# Flash-Memory.net
KiCad netlist of a schematic drawn in Altium Designer
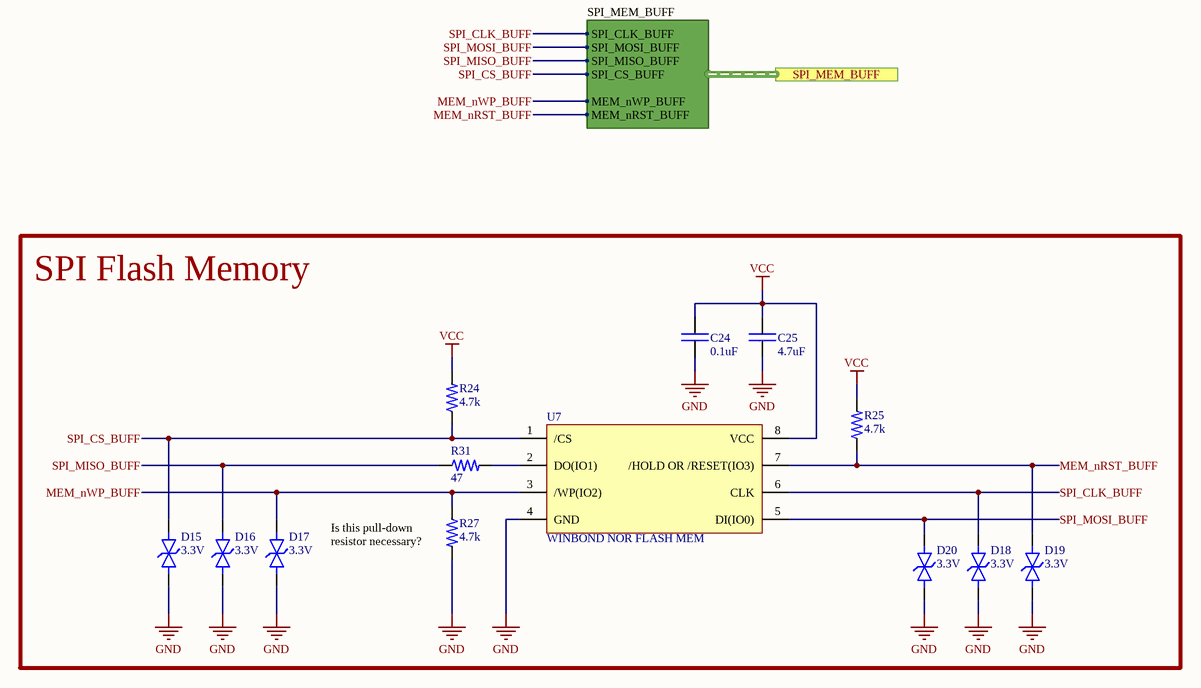
[diagram p0: Flash-Memory.SchDoc]

(export (version "E")
  (design (tool "Eeschema 10.0.6"))
  (components
    (comp (ref "C24")
      (value "0.1uF")
      (footprint "Beethoven-clock:0402C")
      (description "Capacitor")
      (fields (field (name "MFR") "Murata Electronics") (field (name "Comment") "CAP"))
      (libsource (lib "Beethoven-clock") (part "CAP"))
    )
    (comp (ref "C25")
      (value "4.7uF")
      (footprint "Beethoven-clock:0402C")
      (description "Capacitor")
      (fields (field (name "MFR") "Murata Electronics") (field (name "Comment") "CAP"))
      (libsource (lib "Beethoven-clock") (part "CAP"))
    )
    (comp (ref "D15")
      (value "DESD3V3E1BL-7B")
      (footprint "Beethoven-clock:0402-TVS")
      (description "TVS DIODE 3.3VWM 7VC DFN1006-2")
      (fields (field (name "MFR") "Diodes Incorporated") (field (name "VRS") "3.3V"))
      (libsource (lib "Beethoven-clock") (part "TVS Diode 3.3V Bi"))
    )
    (comp (ref "D16")
      (value "DESD3V3E1BL-7B")
      (footprint "Beethoven-clock:0402-TVS")
      (description "TVS DIODE 3.3VWM 7VC DFN1006-2")
      (fields (field (name "MFR") "Diodes Incorporated") (field (name "VRS") "3.3V"))
      (libsource (lib "Beethoven-clock") (part "TVS Diode 3.3V Bi"))
    )
    (comp (ref "D17")
      (value "DESD3V3E1BL-7B")
      (footprint "Beethoven-clock:0402-TVS")
      (description "TVS DIODE 3.3VWM 7VC DFN1006-2")
      (fields (field (name "MFR") "Diodes Incorporated") (field (name "VRS") "3.3V"))
      (libsource (lib "Beethoven-clock") (part "TVS Diode 3.3V Bi"))
    )
    (comp (ref "D18")
      (value "DESD3V3E1BL-7B")
      (footprint "Beethoven-clock:0402-TVS")
      (description "TVS DIODE 3.3VWM 7VC DFN1006-2")
      (fields (field (name "MFR") "Diodes Incorporated") (field (name "VRS") "3.3V"))
      (libsource (lib "Beethoven-clock") (part "TVS Diode 3.3V Bi"))
    )
    (comp (ref "D19")
      (value "DESD3V3E1BL-7B")
      (footprint "Beethoven-clock:0402-TVS")
      (description "TVS DIODE 3.3VWM 7VC DFN1006-2")
      (fields (field (name "MFR") "Diodes Incorporated") (field (name "VRS") "3.3V"))
      (libsource (lib "Beethoven-clock") (part "TVS Diode 3.3V Bi"))
    )
    (comp (ref "D20")
      (value "DESD3V3E1BL-7B")
      (footprint "Beethoven-clock:0402-TVS")
      (description "TVS DIODE 3.3VWM 7VC DFN1006-2")
      (fields (field (name "MFR") "Diodes Incorporated") (field (name "VRS") "3.3V"))
      (libsource (lib "Beethoven-clock") (part "TVS Diode 3.3V Bi"))
    )
    (comp (ref "R24")
      (value "4.7k")
      (footprint "Beethoven-clock:0402R")
      (description "Resistor")
      (fields (field (name "MFR") "YAGEO") (field (name "Comment") "RES"))
      (libsource (lib "Beethoven-clock") (part "RES"))
    )
    (comp (ref "R25")
      (value "4.7k")
      (footprint "Beethoven-clock:0402R")
      (description "Resistor")
      (fields (field (name "MFR") "YAGEO") (field (name "Comment") "RES"))
      (libsource (lib "Beethoven-clock") (part "RES"))
    )
    (comp (ref "R27")
      (value "4.7k")
      (footprint "Beethoven-clock:0402R")
      (description "Resistor")
      (fields (field (name "MFR") "YAGEO") (field (name "Comment") "RES"))
      (libsource (lib "Beethoven-clock") (part "RES"))
    )
    (comp (ref "R31")
      (value "47")
      (footprint "Beethoven-clock:0402R")
      (description "Resistor")
      (fields (field (name "MFR") "YAGEO") (field (name "Comment") "RES"))
      (libsource (lib "Beethoven-clock") (part "RES"))
    )
    (comp (ref "U7")
      (value "WINBOND NOR FLASH MEM")
      (footprint "Beethoven-clock:8-SOIC")
      (description "FLASH - NOR Memory IC SPI")
      (fields (field (name "MFR") "Winbond"))
      (libsource (lib "Beethoven-clock") (part "WINBOND NOR FLASH MEM"))
    )
  )
  (nets
    (net (code "2") (name "/MEM_nRST_BUFF") (class "Default")
      (node (ref "D19") (pin "1") (pinfunction "1_1") (pintype "passive"))
      (node (ref "R25") (pin "1") (pinfunction "1_1") (pintype "passive"))
      (node (ref "U7") (pin "7") (pinfunction "/HOLD_OR_/RESET(IO3)_7") (pintype "passive"))
    )
    (net (code "3") (name "/MEM_nWP_BUFF") (class "Default")
      (node (ref "D17") (pin "1") (pinfunction "1_1") (pintype "passive"))
      (node (ref "R27") (pin "1") (pinfunction "1_1") (pintype "passive"))
      (node (ref "U7") (pin "3") (pinfunction "/WP(IO2)_3") (pintype "passive"))
    )
    (net (code "4") (name "/SPI_CLK_BUFF") (class "Default")
      (node (ref "D18") (pin "1") (pinfunction "1_1") (pintype "passive"))
      (node (ref "U7") (pin "6") (pinfunction "CLK_6") (pintype "passive"))
    )
    (net (code "5") (name "/SPI_CS_BUFF") (class "Default")
      (node (ref "D15") (pin "1") (pinfunction "1_1") (pintype "passive"))
      (node (ref "R24") (pin "1") (pinfunction "1_1") (pintype "passive"))
      (node (ref "U7") (pin "1") (pinfunction "/CS_1") (pintype "passive"))
    )
    (net (code "6") (name "/SPI_MISO_BUFF") (class "Default")
      (node (ref "D16") (pin "1") (pinfunction "1_1") (pintype "passive"))
      (node (ref "R31") (pin "1") (pinfunction "1_1") (pintype "passive"))
    )
    (net (code "7") (name "/SPI_MOSI_BUFF") (class "Default")
      (node (ref "D20") (pin "1") (pinfunction "1_1") (pintype "passive"))
      (node (ref "U7") (pin "5") (pinfunction "DI(IO0)_5") (pintype "passive"))
    )
    (net (code "9") (name "GND") (class "Default")
      (node (ref "C24") (pin "1") (pinfunction "1_1") (pintype "passive"))
      (node (ref "C25") (pin "1") (pinfunction "1_1") (pintype "passive"))
      (node (ref "D15") (pin "2") (pinfunction "2_2") (pintype "passive"))
      (node (ref "D16") (pin "2") (pinfunction "2_2") (pintype "passive"))
      (node (ref "D17") (pin "2") (pinfunction "2_2") (pintype "passive"))
      (node (ref "D18") (pin "2") (pinfunction "2_2") (pintype "passive"))
      (node (ref "D19") (pin "2") (pinfunction "2_2") (pintype "passive"))
      (node (ref "D20") (pin "2") (pinfunction "2_2") (pintype "passive"))
      (node (ref "R27") (pin "2") (pinfunction "2_2") (pintype "passive"))
      (node (ref "U7") (pin "4") (pinfunction "GND_4") (pintype "power_in"))
    )
    (net (code "10") (name "Net-(U7-DO(IO1))") (class "Default")
      (node (ref "R31") (pin "2") (pinfunction "2_2") (pintype "passive"))
      (node (ref "U7") (pin "2") (pinfunction "DO(IO1)_2") (pintype "passive"))
    )
    (net (code "11") (name "VCC") (class "Default")
      (node (ref "C24") (pin "2") (pinfunction "2_2") (pintype "passive"))
      (node (ref "C25") (pin "2") (pinfunction "2_2") (pintype "passive"))
      (node (ref "R24") (pin "2") (pinfunction "2_2") (pintype "passive"))
      (node (ref "R25") (pin "2") (pinfunction "2_2") (pintype "passive"))
      (node (ref "U7") (pin "8") (pinfunction "VCC_8") (pintype "power_in"))
    )
  )
)
